# untitled.net
KiCad netlist of a schematic drawn in EAGLE
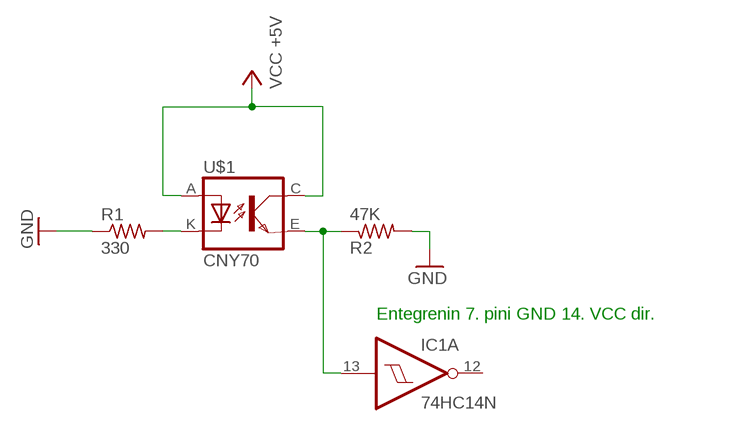
[diagram p0: schematic, sheet 1]

(export (version "E")
  (design (tool "Eeschema 10.0.6"))
  (components
    (comp (ref "IC1")
      (value "74HC14N")
      (footprint "eagle-import:DIL14")
      (libsource (lib "eagle-import") (part "7414NHC"))
    )
    (comp (ref "R1")
      (value "330")
      (footprint "eagle-import:0204_5")
      (libsource (lib "eagle-import") (part "R-US_0204/5"))
    )
    (comp (ref "R2")
      (value "47K")
      (footprint "eagle-import:0204_5")
      (libsource (lib "eagle-import") (part "R-US_0204/5"))
    )
    (comp (ref "U$1")
      (value "CNY70")
      (footprint "eagle-import:4")
      (libsource (lib "eagle-import") (part "CNY70"))
    )
  )
  (nets
    (net (code "1") (name "GND") (class "Default")
      (node (ref "R1") (pin "1") (pinfunction "1_1") (pintype "passive"))
      (node (ref "R2") (pin "2") (pinfunction "2_2") (pintype "passive"))
    )
    (net (code "2") (name "Net-(IC1A-I)") (class "Default")
      (node (ref "IC1") (pin "13") (pinfunction "I_13") (pintype "input"))
      (node (ref "R2") (pin "1") (pinfunction "1_1") (pintype "passive"))
      (node (ref "U$1") (pin "E") (pinfunction "EMI_E") (pintype "passive"))
    )
    (net (code "3") (name "Net-(U$1-C)") (class "Default")
      (node (ref "R1") (pin "2") (pinfunction "2_2") (pintype "passive"))
      (node (ref "U$1") (pin "K") (pinfunction "C_K") (pintype "passive"))
    )
    (net (code "4") (name "VCC +5V") (class "Default")
      (node (ref "U$1") (pin "A") (pinfunction "A_A") (pintype "passive"))
      (node (ref "U$1") (pin "C") (pinfunction "COL_C") (pintype "passive"))
    )
    (net (code "5") (name "unconnected-(IC1A-O-Pad12)") (class "Default")
      (node (ref "IC1") (pin "12") (pinfunction "O_12") (pintype "output"))
    )
  )
)
